# Power_Distribution.net
KiCad netlist of a schematic drawn in EAGLE
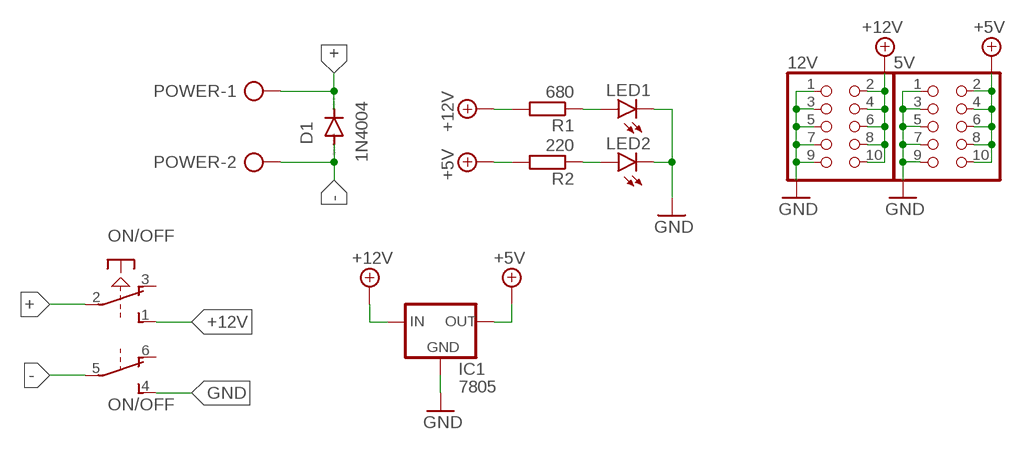
[diagram p0: schematic, sheet 1]

(export (version "E")
  (design (tool "Eeschema 10.0.6"))
  (components
    (comp (ref "5V")
      (value "PINHD-2X5")
      (footprint "eagle-import:2X05")
      (libsource (lib "eagle-import") (part "PINHD-2X5"))
    )
    (comp (ref "12V")
      (value "PINHD-2X5")
      (footprint "eagle-import:2X05")
      (libsource (lib "eagle-import") (part "PINHD-2X5"))
    )
    (comp (ref "D1")
      (value "1N4004")
      (footprint "eagle-import:DO41-10")
      (libsource (lib "eagle-import") (part "1N4004"))
    )
    (comp (ref "IC1")
      (value "7805")
      (footprint "eagle-import:78XXS")
      (libsource (lib "eagle-import") (part "78XXS"))
    )
    (comp (ref "LED1")
      (value "LED3MM")
      (footprint "eagle-import:LED3MM")
      (libsource (lib "eagle-import") (part "LED3MM"))
    )
    (comp (ref "LED2")
      (value "LED3MM")
      (footprint "eagle-import:LED3MM")
      (libsource (lib "eagle-import") (part "LED3MM"))
    )
    (comp (ref "ON/OFF")
      (value "PVA2R")
      (footprint "eagle-import:PVA2R")
      (libsource (lib "eagle-import") (part "PVA2R"))
    )
    (comp (ref "POWER")
      (value "AK500/2-H")
      (footprint "eagle-import:AK500_2-H")
      (libsource (lib "eagle-import") (part "AK500/2-H"))
    )
    (comp (ref "R1")
      (value "680")
      (footprint "eagle-import:0207_10")
      (libsource (lib "eagle-import") (part "R-EU_0207/10"))
    )
    (comp (ref "R2")
      (value "220")
      (footprint "eagle-import:0207_10")
      (libsource (lib "eagle-import") (part "R-EU_0207/10"))
    )
  )
  (nets
    (net (code "1") (name "+") (class "Default")
      (node (ref "D1") (pin "C") (pinfunction "C_C") (pintype "passive"))
      (node (ref "ON/OFF") (pin "2") (pinfunction "P_2") (pintype "passive"))
      (node (ref "POWER") (pin "1") (pinfunction "KL_1") (pintype "passive"))
    )
    (net (code "2") (name "+5V") (class "Default")
      (node (ref "5V") (pin "10") (pinfunction "10_10") (pintype "passive"))
      (node (ref "5V") (pin "2") (pinfunction "2_2") (pintype "passive"))
      (node (ref "5V") (pin "4") (pinfunction "4_4") (pintype "passive"))
      (node (ref "5V") (pin "6") (pinfunction "6_6") (pintype "passive"))
      (node (ref "5V") (pin "8") (pinfunction "8_8") (pintype "passive"))
      (node (ref "IC1") (pin "OUT") (pinfunction "OUT_OUT") (pintype "passive"))
      (node (ref "R2") (pin "2") (pinfunction "2_2") (pintype "passive"))
    )
    (net (code "3") (name "+12V") (class "Default")
      (node (ref "12V") (pin "10") (pinfunction "10_10") (pintype "passive"))
      (node (ref "12V") (pin "2") (pinfunction "2_2") (pintype "passive"))
      (node (ref "12V") (pin "4") (pinfunction "4_4") (pintype "passive"))
      (node (ref "12V") (pin "6") (pinfunction "6_6") (pintype "passive"))
      (node (ref "12V") (pin "8") (pinfunction "8_8") (pintype "passive"))
      (node (ref "IC1") (pin "IN") (pinfunction "IN_IN") (pintype "input"))
      (node (ref "ON/OFF") (pin "1") (pinfunction "S_1") (pintype "passive"))
      (node (ref "R1") (pin "2") (pinfunction "2_2") (pintype "passive"))
    )
    (net (code "4") (name "-") (class "Default")
      (node (ref "D1") (pin "A") (pinfunction "A_A") (pintype "passive"))
      (node (ref "ON/OFF") (pin "5") (pinfunction "P_5") (pintype "passive"))
      (node (ref "POWER") (pin "2") (pinfunction "KL_2") (pintype "passive"))
    )
    (net (code "5") (name "GND") (class "Default")
      (node (ref "12V") (pin "1") (pinfunction "1_1") (pintype "passive"))
      (node (ref "12V") (pin "3") (pinfunction "3_3") (pintype "passive"))
      (node (ref "12V") (pin "5") (pinfunction "5_5") (pintype "passive"))
      (node (ref "12V") (pin "7") (pinfunction "7_7") (pintype "passive"))
      (node (ref "12V") (pin "9") (pinfunction "9_9") (pintype "passive"))
      (node (ref "5V") (pin "1") (pinfunction "1_1") (pintype "passive"))
      (node (ref "5V") (pin "3") (pinfunction "3_3") (pintype "passive"))
      (node (ref "5V") (pin "5") (pinfunction "5_5") (pintype "passive"))
      (node (ref "5V") (pin "7") (pinfunction "7_7") (pintype "passive"))
      (node (ref "5V") (pin "9") (pinfunction "9_9") (pintype "passive"))
      (node (ref "IC1") (pin "GND") (pinfunction "GND_GND") (pintype "input"))
      (node (ref "LED1") (pin "K") (pinfunction "C_K") (pintype "passive"))
      (node (ref "LED2") (pin "K") (pinfunction "C_K") (pintype "passive"))
      (node (ref "ON/OFF") (pin "4") (pinfunction "S_4") (pintype "passive"))
    )
    (net (code "6") (name "Net-(LED1-PadA)") (class "Default")
      (node (ref "LED1") (pin "A") (pinfunction "A_A") (pintype "passive"))
      (node (ref "R1") (pin "1") (pinfunction "1_1") (pintype "passive"))
    )
    (net (code "7") (name "Net-(LED2-PadA)") (class "Default")
      (node (ref "LED2") (pin "A") (pinfunction "A_A") (pintype "passive"))
      (node (ref "R2") (pin "1") (pinfunction "1_1") (pintype "passive"))
    )
    (net (code "8") (name "unconnected-(ON/OFFA-O-Pad3)") (class "Default")
      (node (ref "ON/OFF") (pin "3") (pinfunction "O_3") (pintype "passive"))
    )
    (net (code "9") (name "unconnected-(ON/OFFB-O-Pad6)") (class "Default")
      (node (ref "ON/OFF") (pin "6") (pinfunction "O_6") (pintype "passive"))
    )
  )
)
